# test-cell-one-shot.net
KiCad netlist of a schematic drawn in EAGLE
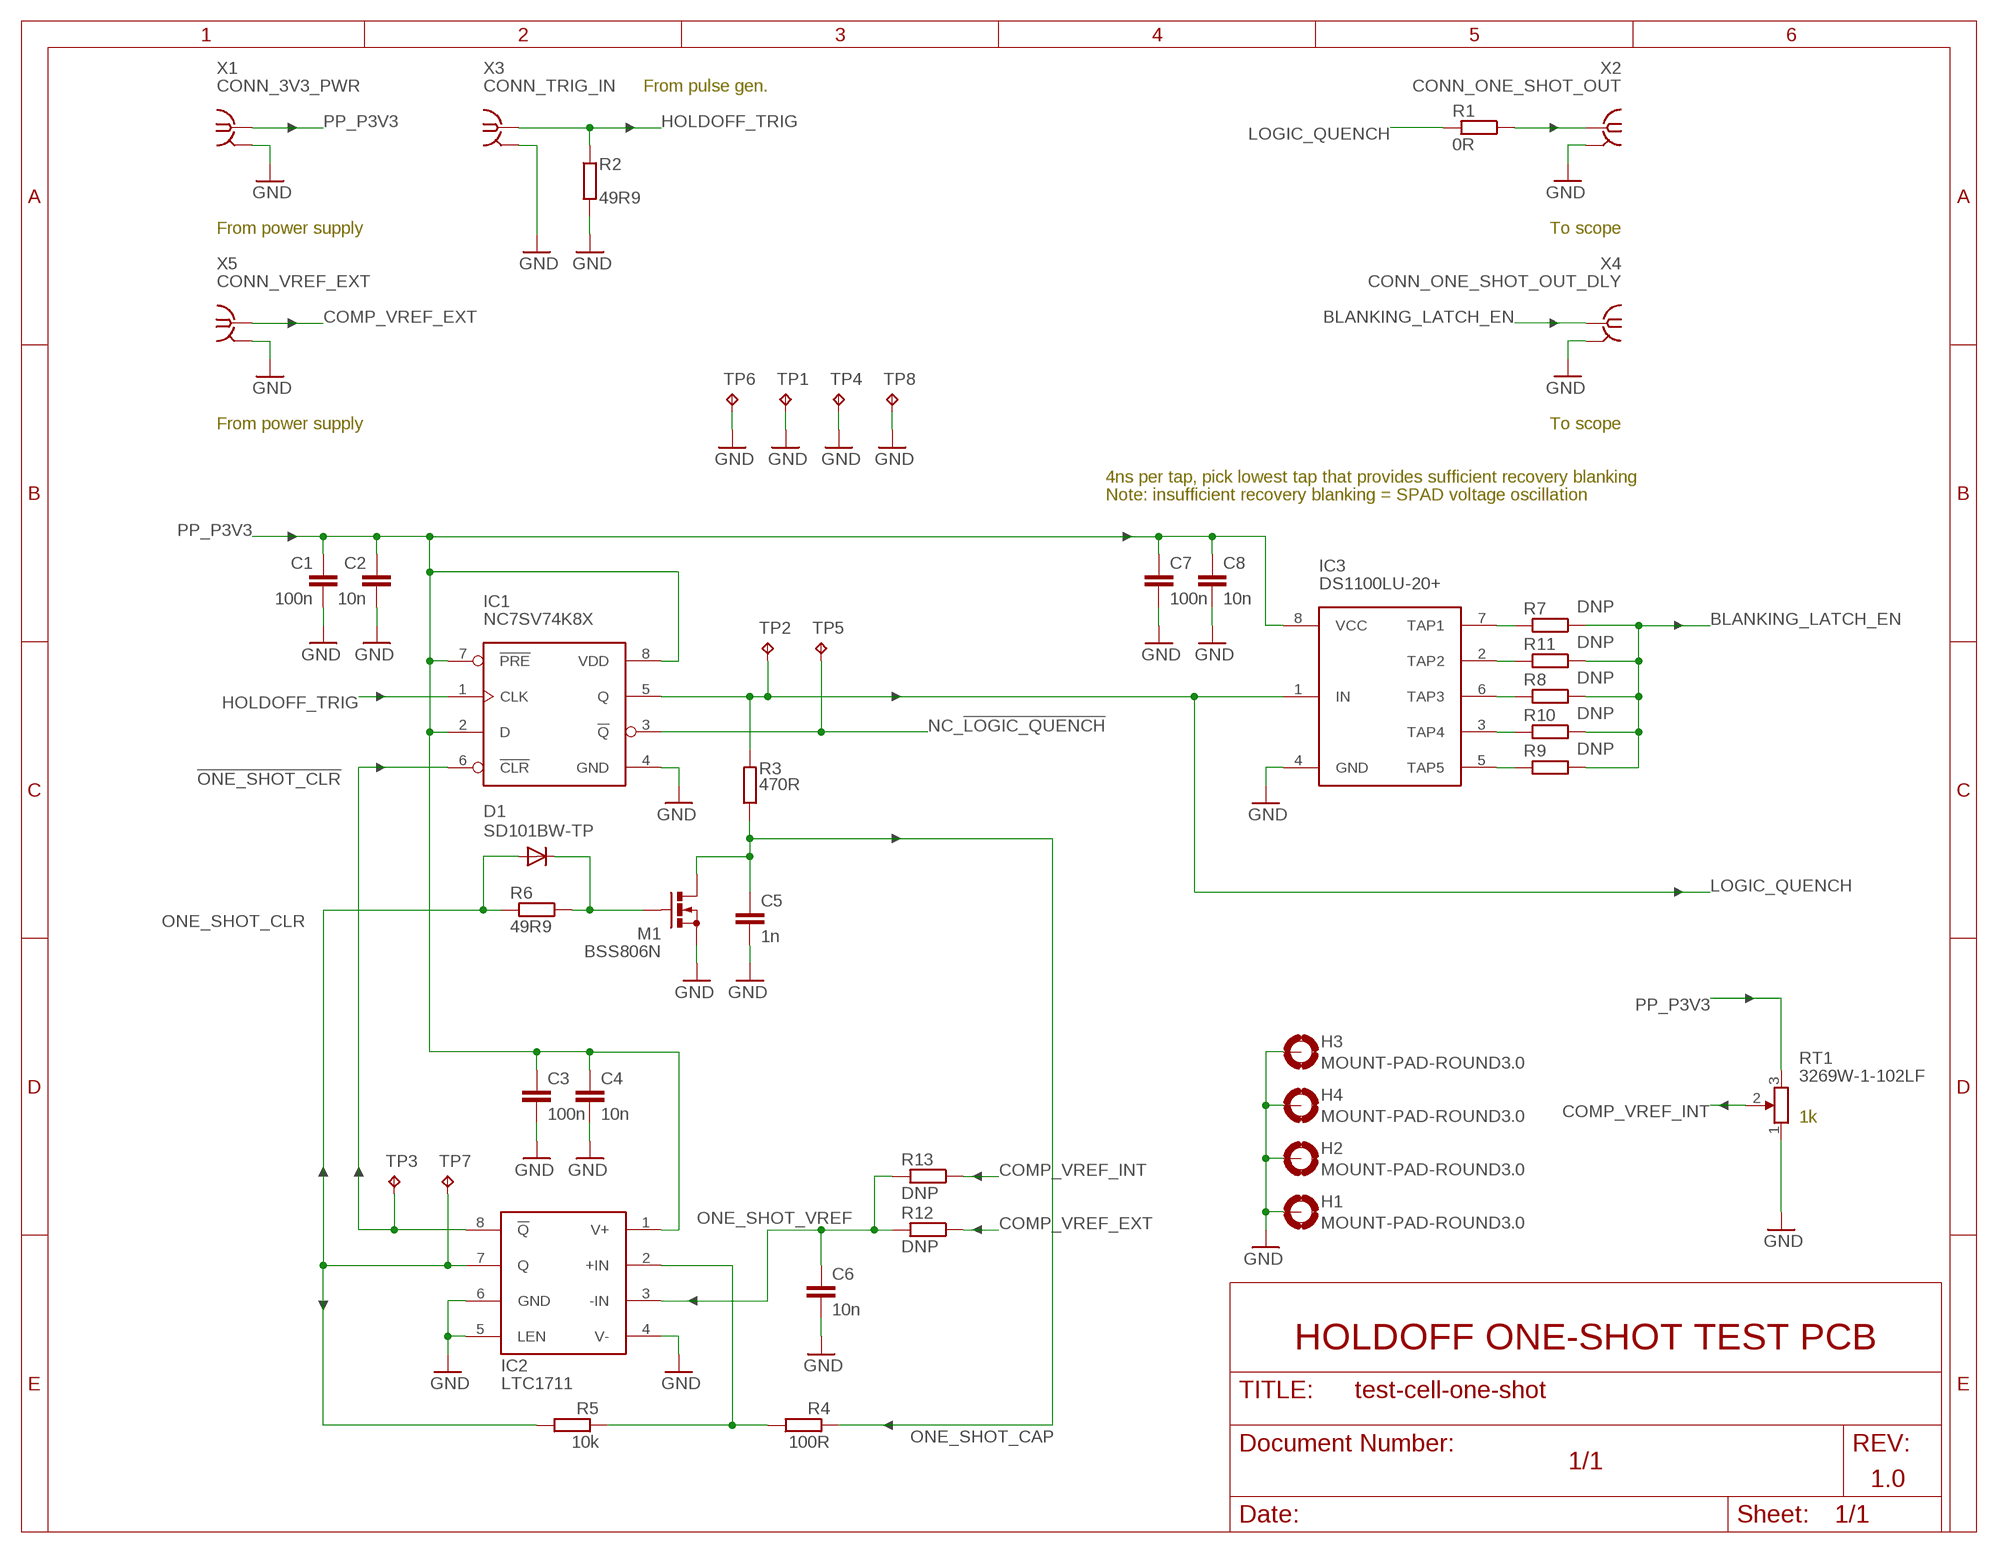
[diagram p0: schematic, sheet 1]

(export (version "E")
  (design (tool "Eeschema 10.0.6"))
  (components
    (comp (ref "C1")
      (value "100n")
      (footprint "eagle-import:C0402")
      (libsource (lib "eagle-import") (part "C-EUC0402"))
    )
    (comp (ref "C2")
      (value "10n")
      (footprint "eagle-import:C0402")
      (libsource (lib "eagle-import") (part "C-EUC0402"))
    )
    (comp (ref "C3")
      (value "100n")
      (footprint "eagle-import:C0402")
      (libsource (lib "eagle-import") (part "C-EUC0402"))
    )
    (comp (ref "C4")
      (value "10n")
      (footprint "eagle-import:C0402")
      (libsource (lib "eagle-import") (part "C-EUC0402"))
    )
    (comp (ref "C5")
      (value "1n")
      (footprint "eagle-import:C0402")
      (libsource (lib "eagle-import") (part "C-EUC0402"))
    )
    (comp (ref "C6")
      (value "10n")
      (footprint "eagle-import:C0402")
      (libsource (lib "eagle-import") (part "C-EUC0402"))
    )
    (comp (ref "C7")
      (value "100n")
      (footprint "eagle-import:C0402")
      (libsource (lib "eagle-import") (part "C-EUC0402"))
    )
    (comp (ref "C8")
      (value "10n")
      (footprint "eagle-import:C0402")
      (libsource (lib "eagle-import") (part "C-EUC0402"))
    )
    (comp (ref "D1")
      (value "SD101BW-TP")
      (footprint "eagle-import:SOD123")
      (libsource (lib "eagle-import") (part "DIODE-SOD123"))
    )
    (comp (ref "H1")
      (value "MOUNT-PAD-ROUND3.0")
      (footprint "eagle-import:3,0-PAD")
      (libsource (lib "eagle-import") (part "MOUNT-PAD-ROUND3.0"))
    )
    (comp (ref "H2")
      (value "MOUNT-PAD-ROUND3.0")
      (footprint "eagle-import:3,0-PAD")
      (libsource (lib "eagle-import") (part "MOUNT-PAD-ROUND3.0"))
    )
    (comp (ref "H3")
      (value "MOUNT-PAD-ROUND3.0")
      (footprint "eagle-import:3,0-PAD")
      (libsource (lib "eagle-import") (part "MOUNT-PAD-ROUND3.0"))
    )
    (comp (ref "H4")
      (value "MOUNT-PAD-ROUND3.0")
      (footprint "eagle-import:3,0-PAD")
      (libsource (lib "eagle-import") (part "MOUNT-PAD-ROUND3.0"))
    )
    (comp (ref "IC1")
      (value "NC7SV74K8X")
      (footprint "eagle-import:US8_3.1MM_JDEC_MO-187")
      (libsource (lib "eagle-import") (part "NC7SV74K8X"))
    )
    (comp (ref "IC2")
      (value "LTC1711")
      (footprint "eagle-import:US8_3.1MM_JDEC_MO-187")
      (libsource (lib "eagle-import") (part "LTC1711"))
    )
    (comp (ref "IC3")
      (value "DS1100LU-20+")
      (footprint "eagle-import:US8_3.1MM_JDEC_MO-187")
      (libsource (lib "eagle-import") (part "DS1100L"))
    )
    (comp (ref "M1")
      (value "BSS806N")
      (footprint "eagle-import:SOT23R_INFINEON")
      (libsource (lib "eagle-import") (part "BSS806N"))
    )
    (comp (ref "R1")
      (value "0R")
      (footprint "eagle-import:R0402")
      (libsource (lib "eagle-import") (part "R-EU_R0402"))
    )
    (comp (ref "R2")
      (value "49R9")
      (footprint "eagle-import:R0603")
      (libsource (lib "eagle-import") (part "R-EU_R0603"))
    )
    (comp (ref "R3")
      (value "470R")
      (footprint "eagle-import:R0402")
      (libsource (lib "eagle-import") (part "R-EU_R0402"))
    )
    (comp (ref "R4")
      (value "100R")
      (footprint "eagle-import:R0402")
      (libsource (lib "eagle-import") (part "R-EU_R0402"))
    )
    (comp (ref "R5")
      (value "10k")
      (footprint "eagle-import:R0402")
      (libsource (lib "eagle-import") (part "R-EU_R0402"))
    )
    (comp (ref "R6")
      (value "49R9")
      (footprint "eagle-import:R0402")
      (libsource (lib "eagle-import") (part "R-EU_R0402"))
    )
    (comp (ref "R7")
      (value "DNP")
      (footprint "eagle-import:R0402")
      (libsource (lib "eagle-import") (part "R-EU_R0402"))
    )
    (comp (ref "R8")
      (value "DNP")
      (footprint "eagle-import:R0402")
      (libsource (lib "eagle-import") (part "R-EU_R0402"))
    )
    (comp (ref "R9")
      (value "DNP")
      (footprint "eagle-import:R0402")
      (libsource (lib "eagle-import") (part "R-EU_R0402"))
    )
    (comp (ref "R10")
      (value "DNP")
      (footprint "eagle-import:R0402")
      (libsource (lib "eagle-import") (part "R-EU_R0402"))
    )
    (comp (ref "R11")
      (value "DNP")
      (footprint "eagle-import:R0402")
      (libsource (lib "eagle-import") (part "R-EU_R0402"))
    )
    (comp (ref "R12")
      (value "DNP")
      (footprint "eagle-import:R0402")
      (libsource (lib "eagle-import") (part "R-EU_R0402"))
    )
    (comp (ref "R13")
      (value "DNP")
      (footprint "eagle-import:R0402")
      (libsource (lib "eagle-import") (part "R-EU_R0402"))
    )
    (comp (ref "RT1")
      (value "3269W-1-102LF")
      (footprint "eagle-import:3269W")
      (libsource (lib "eagle-import") (part "BOURNS_3269WX"))
    )
    (comp (ref "TP1")
      (value "TPTP10R")
      (footprint "eagle-import:TP10R")
      (libsource (lib "eagle-import") (part "TPTP10R"))
    )
    (comp (ref "TP2")
      (value "TPTP10R")
      (footprint "eagle-import:TP10R")
      (libsource (lib "eagle-import") (part "TPTP10R"))
    )
    (comp (ref "TP3")
      (value "TPTP10R")
      (footprint "eagle-import:TP10R")
      (libsource (lib "eagle-import") (part "TPTP10R"))
    )
    (comp (ref "TP4")
      (value "TPTP10R")
      (footprint "eagle-import:TP10R")
      (libsource (lib "eagle-import") (part "TPTP10R"))
    )
    (comp (ref "TP5")
      (value "TPTP10R")
      (footprint "eagle-import:TP10R")
      (libsource (lib "eagle-import") (part "TPTP10R"))
    )
    (comp (ref "TP6")
      (value "TPTP10R")
      (footprint "eagle-import:TP10R")
      (libsource (lib "eagle-import") (part "TPTP10R"))
    )
    (comp (ref "TP7")
      (value "TPTP10R")
      (footprint "eagle-import:TP10R")
      (libsource (lib "eagle-import") (part "TPTP10R"))
    )
    (comp (ref "TP8")
      (value "TPTP10R")
      (footprint "eagle-import:TP10R")
      (libsource (lib "eagle-import") (part "TPTP10R"))
    )
    (comp (ref "X1")
      (value "CONN_3V3_PWR")
      (footprint "eagle-import:J502-ND-142-0711-871_876")
      (fields (field (name "MF") "JOHNSON COMPONENTS") (field (name "MPN") "142-0711-871"))
      (libsource (lib "eagle-import") (part "SMA-142-0711-871/876"))
    )
    (comp (ref "X2")
      (value "CONN_ONE_SHOT_OUT")
      (footprint "eagle-import:J502-ND-142-0711-871_876")
      (fields (field (name "MF") "JOHNSON COMPONENTS") (field (name "MPN") "142-0711-871"))
      (libsource (lib "eagle-import") (part "SMA-142-0711-871/876"))
    )
    (comp (ref "X3")
      (value "CONN_TRIG_IN")
      (footprint "eagle-import:J502-ND-142-0711-871_876")
      (fields (field (name "MF") "JOHNSON COMPONENTS") (field (name "MPN") "142-0711-871"))
      (libsource (lib "eagle-import") (part "SMA-142-0711-871/876"))
    )
    (comp (ref "X4")
      (value "CONN_ONE_SHOT_OUT_DLY")
      (footprint "eagle-import:J502-ND-142-0711-871_876")
      (fields (field (name "MF") "JOHNSON COMPONENTS") (field (name "MPN") "142-0711-871"))
      (libsource (lib "eagle-import") (part "SMA-142-0711-871/876"))
    )
    (comp (ref "X5")
      (value "CONN_VREF_EXT")
      (footprint "eagle-import:J502-ND-142-0711-871_876")
      (fields (field (name "MF") "JOHNSON COMPONENTS") (field (name "MPN") "142-0711-871"))
      (libsource (lib "eagle-import") (part "SMA-142-0711-871/876"))
    )
  )
  (nets
    (net (code "1") (name "/BLANKING_LATCH_EN") (class "Default")
      (node (ref "R10") (pin "1") (pinfunction "1_1") (pintype "passive"))
      (node (ref "R11") (pin "1") (pinfunction "1_1") (pintype "passive"))
      (node (ref "R7") (pin "1") (pinfunction "1_1") (pintype "passive"))
      (node (ref "R8") (pin "1") (pinfunction "1_1") (pintype "passive"))
      (node (ref "R9") (pin "1") (pinfunction "1_1") (pintype "passive"))
      (node (ref "X4") (pin "1") (pinfunction "1_1") (pintype "passive"))
    )
    (net (code "2") (name "/COMP_VREF_EXT") (class "Default")
      (node (ref "R12") (pin "1") (pinfunction "1_1") (pintype "passive"))
      (node (ref "X5") (pin "1") (pinfunction "1_1") (pintype "passive"))
    )
    (net (code "3") (name "/COMP_VREF_INT") (class "Default")
      (node (ref "R13") (pin "1") (pinfunction "1_1") (pintype "passive"))
      (node (ref "RT1") (pin "2") (pinfunction "2_2") (pintype "bidirectional"))
    )
    (net (code "4") (name "/HOLDOFF_TRIG") (class "Default")
      (node (ref "IC1") (pin "1") (pinfunction "CLK_1") (pintype "bidirectional"))
      (node (ref "R2") (pin "1") (pinfunction "1_1") (pintype "passive"))
      (node (ref "X3") (pin "1") (pinfunction "1_1") (pintype "passive"))
    )
    (net (code "5") (name "/LOGIC_QUENCH") (class "Default")
      (node (ref "IC1") (pin "5") (pinfunction "Q_5") (pintype "bidirectional"))
      (node (ref "IC3") (pin "1") (pinfunction "IN_1") (pintype "bidirectional"))
      (node (ref "R1") (pin "2") (pinfunction "2_2") (pintype "passive"))
      (node (ref "R3") (pin "2") (pinfunction "2_2") (pintype "passive"))
      (node (ref "TP2") (pin "TP") (pinfunction "TP_TP") (pintype "input"))
    )
    (net (code "6") (name "/NC_~{LOGIC_QUENCH}") (class "Default")
      (node (ref "IC1") (pin "3") (pinfunction "~{Q}_3") (pintype "bidirectional"))
      (node (ref "TP5") (pin "TP") (pinfunction "TP_TP") (pintype "input"))
    )
    (net (code "7") (name "/ONE_SHOT_CAP") (class "Default")
      (node (ref "C5") (pin "1") (pinfunction "1_1") (pintype "passive"))
      (node (ref "M1") (pin "3") (pinfunction "D_3") (pintype "passive"))
      (node (ref "R3") (pin "1") (pinfunction "1_1") (pintype "passive"))
      (node (ref "R4") (pin "2") (pinfunction "2_2") (pintype "passive"))
    )
    (net (code "8") (name "/ONE_SHOT_CLR") (class "Default")
      (node (ref "D1") (pin "A") (pinfunction "A_A") (pintype "passive"))
      (node (ref "IC2") (pin "7") (pinfunction "Q_7") (pintype "bidirectional"))
      (node (ref "R5") (pin "1") (pinfunction "1_1") (pintype "passive"))
      (node (ref "R6") (pin "2") (pinfunction "2_2") (pintype "passive"))
      (node (ref "TP7") (pin "TP") (pinfunction "TP_TP") (pintype "input"))
    )
    (net (code "9") (name "/ONE_SHOT_VREF") (class "Default")
      (node (ref "C6") (pin "1") (pinfunction "1_1") (pintype "passive"))
      (node (ref "IC2") (pin "3") (pinfunction "-IN_3") (pintype "bidirectional"))
      (node (ref "R12") (pin "2") (pinfunction "2_2") (pintype "passive"))
      (node (ref "R13") (pin "2") (pinfunction "2_2") (pintype "passive"))
    )
    (net (code "10") (name "/PP_P3V3") (class "Default")
      (node (ref "C1") (pin "1") (pinfunction "1_1") (pintype "passive"))
      (node (ref "C2") (pin "1") (pinfunction "1_1") (pintype "passive"))
      (node (ref "C3") (pin "1") (pinfunction "1_1") (pintype "passive"))
      (node (ref "C4") (pin "1") (pinfunction "1_1") (pintype "passive"))
      (node (ref "C7") (pin "1") (pinfunction "1_1") (pintype "passive"))
      (node (ref "C8") (pin "1") (pinfunction "1_1") (pintype "passive"))
      (node (ref "IC1") (pin "2") (pinfunction "D_2") (pintype "bidirectional"))
      (node (ref "IC1") (pin "7") (pinfunction "~{PRE}_7") (pintype "bidirectional"))
      (node (ref "IC1") (pin "8") (pinfunction "VDD_8") (pintype "bidirectional"))
      (node (ref "IC2") (pin "1") (pinfunction "V+_1") (pintype "bidirectional"))
      (node (ref "IC3") (pin "8") (pinfunction "VCC_8") (pintype "bidirectional"))
      (node (ref "RT1") (pin "3") (pinfunction "3_3") (pintype "bidirectional"))
      (node (ref "X1") (pin "1") (pinfunction "1_1") (pintype "passive"))
    )
    (net (code "11") (name "/~{ONE_SHOT_CLR}") (class "Default")
      (node (ref "IC1") (pin "6") (pinfunction "~{CLR}_6") (pintype "bidirectional"))
      (node (ref "IC2") (pin "8") (pinfunction "~{Q}_8") (pintype "bidirectional"))
      (node (ref "TP3") (pin "TP") (pinfunction "TP_TP") (pintype "input"))
    )
    (net (code "12") (name "GND") (class "Default")
      (node (ref "C1") (pin "2") (pinfunction "2_2") (pintype "passive"))
      (node (ref "C2") (pin "2") (pinfunction "2_2") (pintype "passive"))
      (node (ref "C3") (pin "2") (pinfunction "2_2") (pintype "passive"))
      (node (ref "C4") (pin "2") (pinfunction "2_2") (pintype "passive"))
      (node (ref "C5") (pin "2") (pinfunction "2_2") (pintype "passive"))
      (node (ref "C6") (pin "2") (pinfunction "2_2") (pintype "passive"))
      (node (ref "C7") (pin "2") (pinfunction "2_2") (pintype "passive"))
      (node (ref "C8") (pin "2") (pinfunction "2_2") (pintype "passive"))
      (node (ref "H1") (pin "B3,0") (pinfunction "MOUNT_B3,0") (pintype "passive"))
      (node (ref "H2") (pin "B3,0") (pinfunction "MOUNT_B3,0") (pintype "passive"))
      (node (ref "H3") (pin "B3,0") (pinfunction "MOUNT_B3,0") (pintype "passive"))
      (node (ref "H4") (pin "B3,0") (pinfunction "MOUNT_B3,0") (pintype "passive"))
      (node (ref "IC1") (pin "4") (pinfunction "GND_4") (pintype "bidirectional"))
      (node (ref "IC2") (pin "4") (pinfunction "V-_4") (pintype "bidirectional"))
      (node (ref "IC2") (pin "5") (pinfunction "LEN_5") (pintype "bidirectional"))
      (node (ref "IC2") (pin "6") (pinfunction "GND_6") (pintype "bidirectional"))
      (node (ref "IC3") (pin "4") (pinfunction "GND_4") (pintype "bidirectional"))
      (node (ref "M1") (pin "2") (pinfunction "S_2") (pintype "passive"))
      (node (ref "R2") (pin "2") (pinfunction "2_2") (pintype "passive"))
      (node (ref "RT1") (pin "1") (pinfunction "1_1") (pintype "bidirectional"))
      (node (ref "TP1") (pin "TP") (pinfunction "TP_TP") (pintype "input"))
      (node (ref "TP4") (pin "TP") (pinfunction "TP_TP") (pintype "input"))
      (node (ref "TP6") (pin "TP") (pinfunction "TP_TP") (pintype "input"))
      (node (ref "TP8") (pin "TP") (pinfunction "TP_TP") (pintype "input"))
      (node (ref "X1") (pin "G@1") (pinfunction "GND_G@1") (pintype "power_in"))
      (node (ref "X2") (pin "G@1") (pinfunction "GND_G@1") (pintype "power_in"))
      (node (ref "X3") (pin "G@1") (pinfunction "GND_G@1") (pintype "power_in"))
      (node (ref "X4") (pin "G@1") (pinfunction "GND_G@1") (pintype "power_in"))
      (node (ref "X5") (pin "G@1") (pinfunction "GND_G@1") (pintype "power_in"))
    )
    (net (code "13") (name "Net-(IC2-+IN)") (class "Default")
      (node (ref "IC2") (pin "2") (pinfunction "+IN_2") (pintype "bidirectional"))
      (node (ref "R4") (pin "1") (pinfunction "1_1") (pintype "passive"))
      (node (ref "R5") (pin "2") (pinfunction "2_2") (pintype "passive"))
    )
    (net (code "14") (name "Net-(IC3-TAP1)") (class "Default")
      (node (ref "IC3") (pin "7") (pinfunction "TAP1_7") (pintype "bidirectional"))
      (node (ref "R7") (pin "2") (pinfunction "2_2") (pintype "passive"))
    )
    (net (code "15") (name "Net-(IC3-TAP2)") (class "Default")
      (node (ref "IC3") (pin "2") (pinfunction "TAP2_2") (pintype "bidirectional"))
      (node (ref "R11") (pin "2") (pinfunction "2_2") (pintype "passive"))
    )
    (net (code "16") (name "Net-(IC3-TAP3)") (class "Default")
      (node (ref "IC3") (pin "6") (pinfunction "TAP3_6") (pintype "bidirectional"))
      (node (ref "R8") (pin "2") (pinfunction "2_2") (pintype "passive"))
    )
    (net (code "17") (name "Net-(IC3-TAP4)") (class "Default")
      (node (ref "IC3") (pin "3") (pinfunction "TAP4_3") (pintype "bidirectional"))
      (node (ref "R10") (pin "2") (pinfunction "2_2") (pintype "passive"))
    )
    (net (code "18") (name "Net-(IC3-TAP5)") (class "Default")
      (node (ref "IC3") (pin "5") (pinfunction "TAP5_5") (pintype "bidirectional"))
      (node (ref "R9") (pin "2") (pinfunction "2_2") (pintype "passive"))
    )
    (net (code "19") (name "Net-(M1-G)") (class "Default")
      (node (ref "D1") (pin "C") (pinfunction "C_C") (pintype "passive"))
      (node (ref "M1") (pin "1") (pinfunction "G_1") (pintype "passive"))
      (node (ref "R6") (pin "1") (pinfunction "1_1") (pintype "passive"))
    )
    (net (code "20") (name "Net-(R1-Pad1)") (class "Default")
      (node (ref "R1") (pin "1") (pinfunction "1_1") (pintype "passive"))
      (node (ref "X2") (pin "1") (pinfunction "1_1") (pintype "passive"))
    )
  )
)
